# ScreenAdapterBoard.net
KiCad netlist of a schematic drawn in Altium Designer
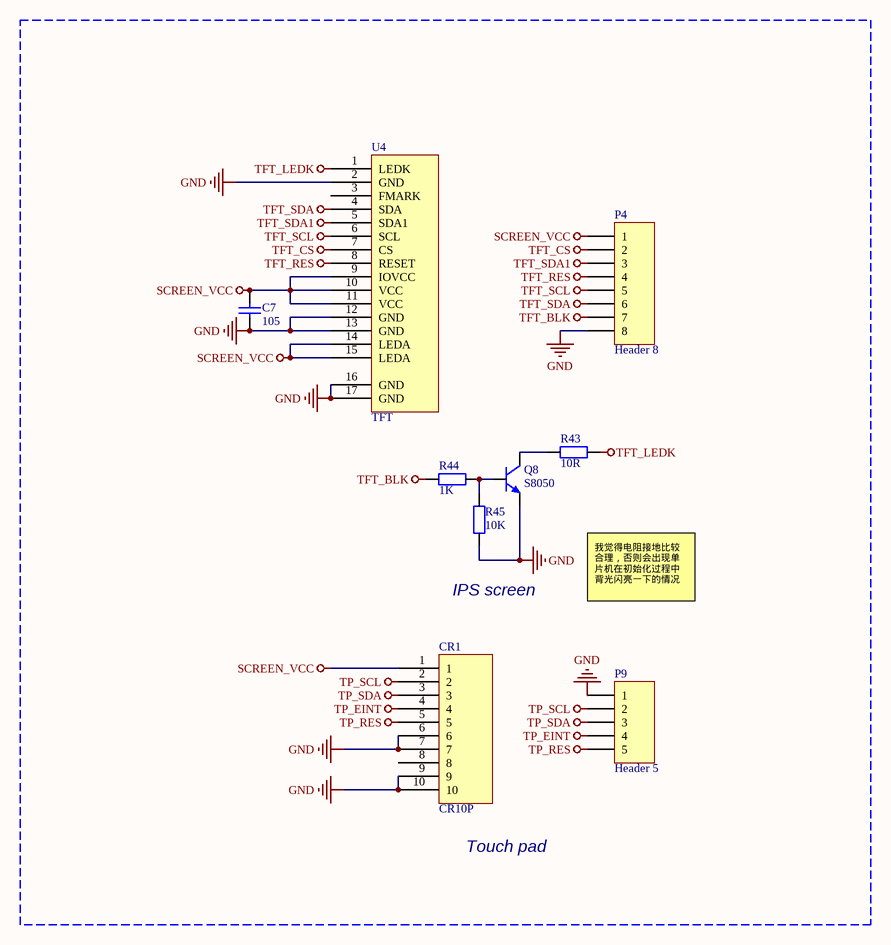
[diagram p0: ScreenAdapterBoard.SchDoc]

(export (version "E")
  (design (tool "Eeschema 10.0.6"))
  (components
    (comp (ref "C7")
      (value "105")
      (footprint "电容_C0603")
      (fields (field (name "C") "105"))
      (libsource (lib "元件库") (part "cap"))
    )
    (comp (ref "CR1")
      (value "CR10P")
      (footprint "TriggersLib:CONN RCPT 10POS 0.4MM")
      (description "板对板连接器")
      (libsource (lib "TriggersLib") (part "CONN RCPT 10P"))
    )
    (comp (ref "P4")
      (value "Header 8")
      (footprint "HDR1X8")
      (description "Header, 8-Pin")
      (fields (field (name "PUBLISHER") "Altium Limited"))
      (libsource (lib "Miscellaneous Connectors") (part "Header 8"))
    )
    (comp (ref "P9")
      (value "Header 5")
      (footprint "HDR1X5")
      (description "Header, 5-Pin")
      (fields (field (name "PUBLISHER") "Altium Limited"))
      (libsource (lib "Miscellaneous Connectors") (part "Header 5"))
    )
    (comp (ref "Q8")
      (value "S8050")
      (footprint "三极管_SOT-23")
      (fields (field (name "_MODEL") "S8050"))
      (libsource (lib "元件库") (part "Triode-NPN"))
    )
    (comp (ref "R43")
      (value "10R")
      (footprint "电阻_R0603")
      (fields (field (name "_VALUE") "10R"))
      (libsource (lib "元件库") (part "Res"))
    )
    (comp (ref "R44")
      (value "1K")
      (footprint "电阻_R0603")
      (fields (field (name "_VALUE") "1K"))
      (libsource (lib "元件库") (part "Res"))
    )
    (comp (ref "R45")
      (value "10K")
      (footprint "电阻_R0603")
      (fields (field (name "_VALUE") "10K"))
      (libsource (lib "") (part "Res_1"))
    )
    (comp (ref "U4")
      (value "TFT")
      (footprint "TriggersLib:FPC-0.30mm-15P")
      (description "IPS电容式触摸屏")
      (libsource (lib "TriggersLib") (part "TFT_IPS1-1.54寸240*240-AML015410V1"))
    )
  )
  (nets
    (net (code "1") (name "GND") (class "Default")
      (node (ref "C7") (pin "2") (pinfunction "2_2") (pintype "passive"))
      (node (ref "CR1") (pin "10") (pinfunction "10_10") (pintype "passive"))
      (node (ref "CR1") (pin "6") (pinfunction "6_6") (pintype "passive"))
      (node (ref "CR1") (pin "7") (pinfunction "7_7") (pintype "passive"))
      (node (ref "CR1") (pin "9") (pinfunction "9_9") (pintype "passive"))
      (node (ref "P4") (pin "8") (pinfunction "8_8") (pintype "passive"))
      (node (ref "P9") (pin "1") (pinfunction "1_1") (pintype "passive"))
      (node (ref "Q8") (pin "3") (pinfunction "E_3") (pintype "passive"))
      (node (ref "R45") (pin "1") (pinfunction "1_1") (pintype "passive"))
      (node (ref "U4") (pin "12") (pinfunction "GND_12") (pintype "passive"))
      (node (ref "U4") (pin "13") (pinfunction "GND_13") (pintype "passive"))
      (node (ref "U4") (pin "16") (pinfunction "GND_16") (pintype "passive"))
      (node (ref "U4") (pin "17") (pinfunction "GND_17") (pintype "passive"))
      (node (ref "U4") (pin "2") (pinfunction "GND_2") (pintype "passive"))
    )
    (net (code "2") (name "Net-(Q8-B)") (class "Default")
      (node (ref "Q8") (pin "1") (pinfunction "B_1") (pintype "passive"))
      (node (ref "R44") (pin "2") (pinfunction "2_2") (pintype "passive"))
      (node (ref "R45") (pin "2") (pinfunction "2_2") (pintype "passive"))
    )
    (net (code "3") (name "Net-(Q8-C)") (class "Default")
      (node (ref "Q8") (pin "2") (pinfunction "C_2") (pintype "passive"))
      (node (ref "R43") (pin "1") (pinfunction "1_1") (pintype "passive"))
    )
    (net (code "4") (name "SCREEN_VCC") (class "Default")
      (node (ref "C7") (pin "1") (pinfunction "1_1") (pintype "passive"))
      (node (ref "CR1") (pin "1") (pinfunction "1_1") (pintype "passive"))
      (node (ref "P4") (pin "1") (pinfunction "1_1") (pintype "passive"))
      (node (ref "U4") (pin "10") (pinfunction "VCC_10") (pintype "passive"))
      (node (ref "U4") (pin "11") (pinfunction "VCC_11") (pintype "passive"))
      (node (ref "U4") (pin "14") (pinfunction "LEDA_14") (pintype "passive"))
      (node (ref "U4") (pin "15") (pinfunction "LEDA_15") (pintype "passive"))
      (node (ref "U4") (pin "9") (pinfunction "IOVCC_9") (pintype "passive"))
    )
    (net (code "5") (name "TFT_BLK") (class "Default")
      (node (ref "P4") (pin "7") (pinfunction "7_7") (pintype "passive"))
      (node (ref "R44") (pin "1") (pinfunction "1_1") (pintype "passive"))
    )
    (net (code "6") (name "TFT_CS") (class "Default")
      (node (ref "P4") (pin "2") (pinfunction "2_2") (pintype "passive"))
      (node (ref "U4") (pin "7") (pinfunction "CS_7") (pintype "passive"))
    )
    (net (code "7") (name "TFT_LEDK") (class "Default")
      (node (ref "R43") (pin "2") (pinfunction "2_2") (pintype "passive"))
      (node (ref "U4") (pin "1") (pinfunction "LEDK_1") (pintype "passive"))
    )
    (net (code "8") (name "TFT_RES") (class "Default")
      (node (ref "P4") (pin "4") (pinfunction "4_4") (pintype "passive"))
      (node (ref "U4") (pin "8") (pinfunction "RESET_8") (pintype "passive"))
    )
    (net (code "9") (name "TFT_SCL") (class "Default")
      (node (ref "P4") (pin "5") (pinfunction "5_5") (pintype "passive"))
      (node (ref "U4") (pin "6") (pinfunction "SCL_6") (pintype "passive"))
    )
    (net (code "10") (name "TFT_SDA") (class "Default")
      (node (ref "P4") (pin "6") (pinfunction "6_6") (pintype "passive"))
      (node (ref "U4") (pin "4") (pinfunction "SDA_4") (pintype "passive"))
    )
    (net (code "11") (name "TFT_SDA1") (class "Default")
      (node (ref "P4") (pin "3") (pinfunction "3_3") (pintype "passive"))
      (node (ref "U4") (pin "5") (pinfunction "SDA1_5") (pintype "passive"))
    )
    (net (code "12") (name "TP_EINT") (class "Default")
      (node (ref "CR1") (pin "4") (pinfunction "4_4") (pintype "passive"))
      (node (ref "P9") (pin "4") (pinfunction "4_4") (pintype "passive"))
    )
    (net (code "13") (name "TP_RES") (class "Default")
      (node (ref "CR1") (pin "5") (pinfunction "5_5") (pintype "passive"))
      (node (ref "P9") (pin "5") (pinfunction "5_5") (pintype "passive"))
    )
    (net (code "14") (name "TP_SCL") (class "Default")
      (node (ref "CR1") (pin "2") (pinfunction "2_2") (pintype "passive"))
      (node (ref "P9") (pin "2") (pinfunction "2_2") (pintype "passive"))
    )
    (net (code "15") (name "TP_SDA") (class "Default")
      (node (ref "CR1") (pin "3") (pinfunction "3_3") (pintype "passive"))
      (node (ref "P9") (pin "3") (pinfunction "3_3") (pintype "passive"))
    )
    (net (code "16") (name "unconnected-(CR1-Pad8)") (class "Default")
      (node (ref "CR1") (pin "8") (pinfunction "8_8") (pintype "passive"))
    )
    (net (code "17") (name "unconnected-(U4-FMARK-Pad3)") (class "Default")
      (node (ref "U4") (pin "3") (pinfunction "FMARK_3") (pintype "passive"))
    )
  )
)
